# DIGITAL_IO.net
KiCad netlist of a schematic drawn in Altium Designer
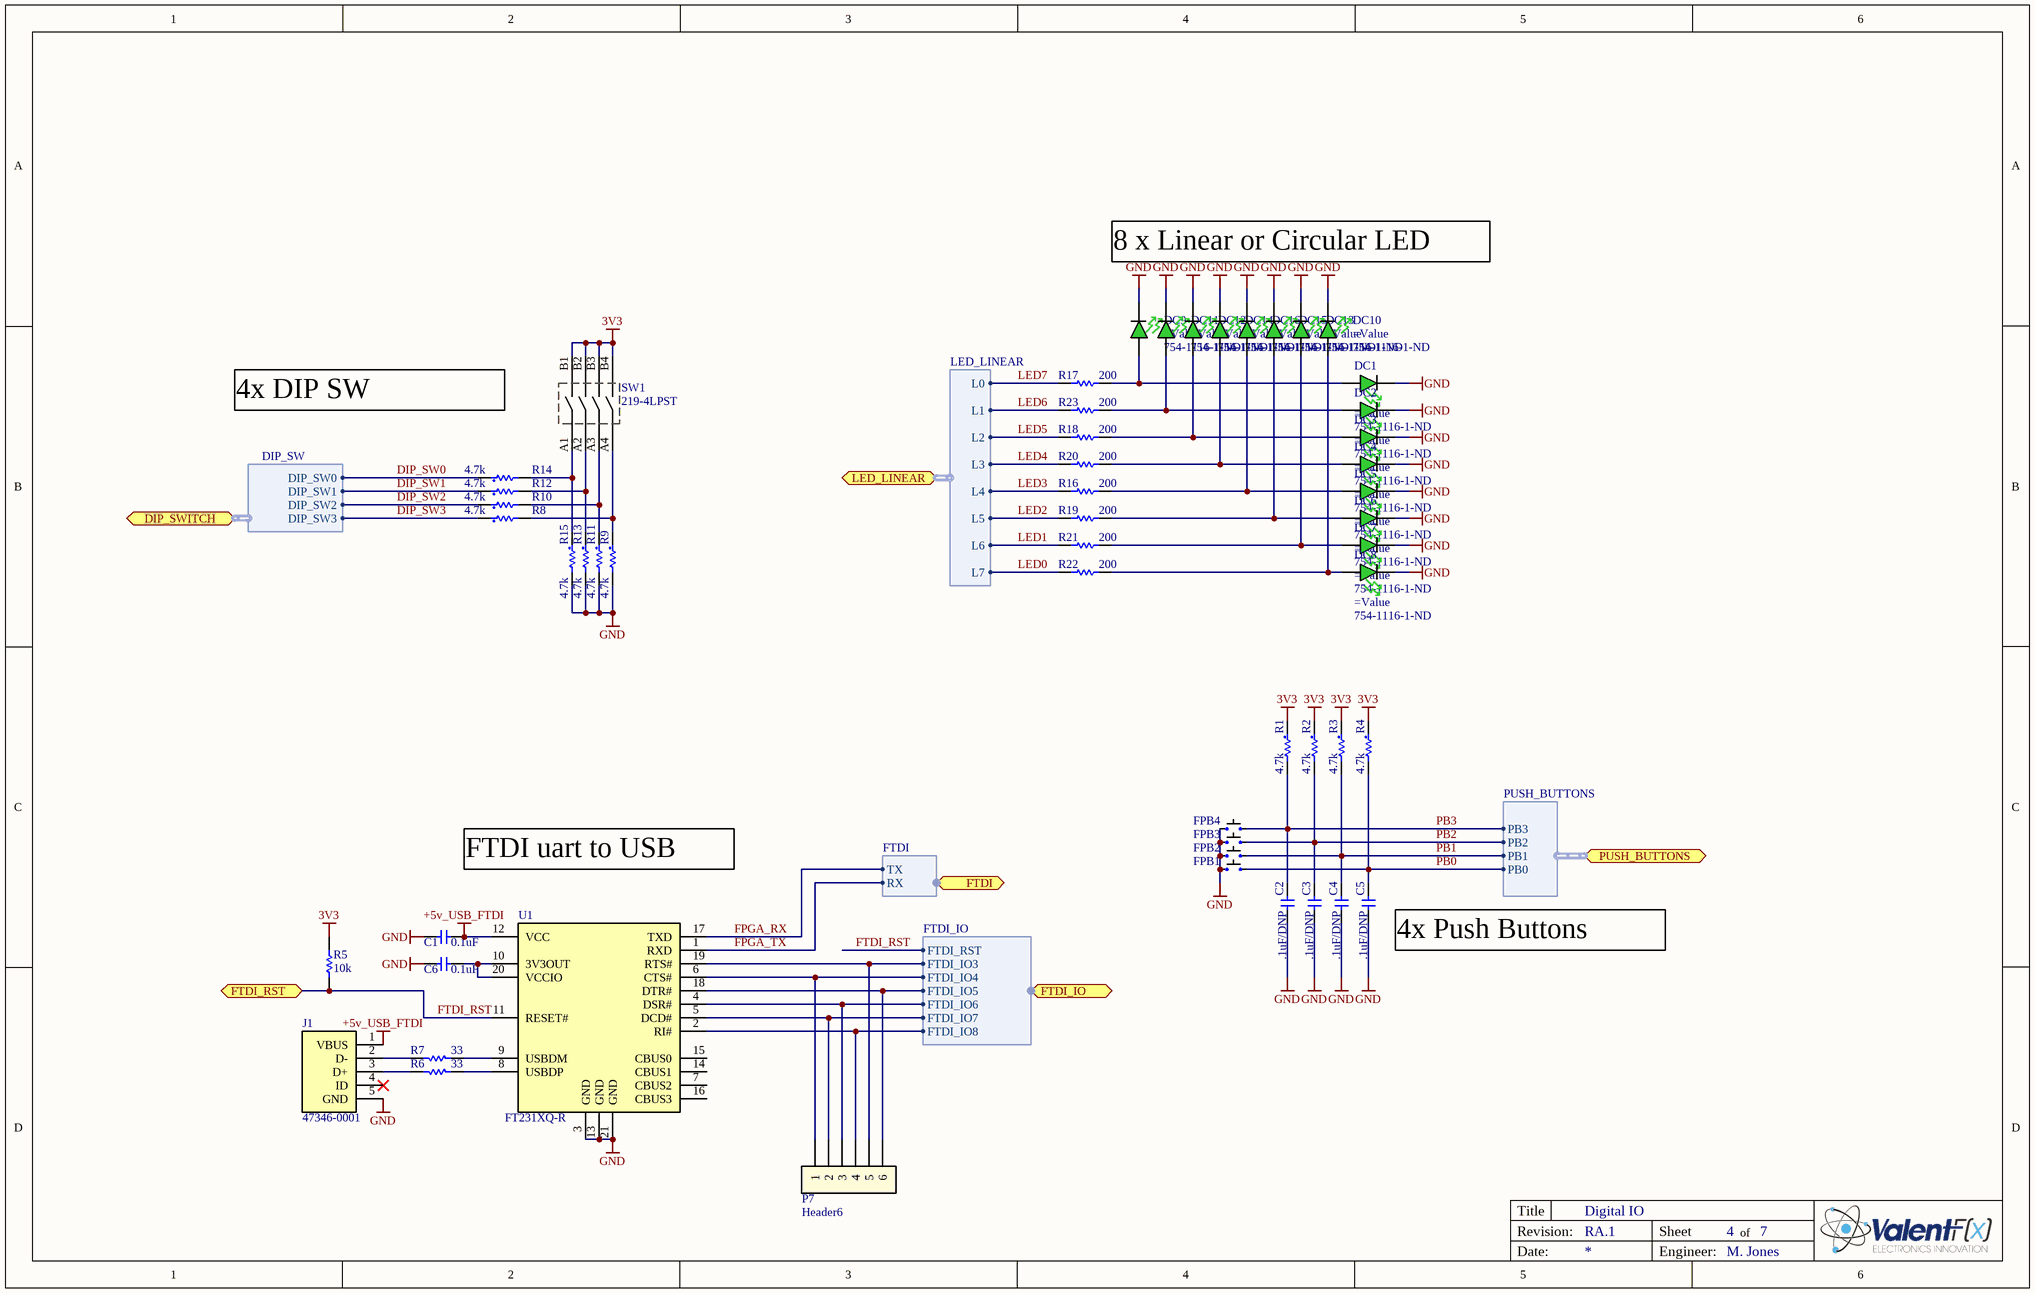
[diagram p0: DIGITAL_IO.SchDoc]

(export (version "E")
  (design (tool "Eeschema 10.0.6"))
  (components
    (comp (ref "C1")
      (value "0.1uF")
      (footprint "C0603")
      (description "CAP CER .1UF 50V 10% X7R 0603")
      (fields
        (field (name "MANUFACTURER") "Murata Electronics North America")
        (field (name "MANUFACTURER PART NUMBER") "GRM188R71H104KA93D")
      )
      (libsource (lib "Capacitors") (part "GRM188R71H104KA93D"))
    )
    (comp (ref "C2")
      (value ".1uF/DNP")
      (footprint "C0603")
      (description "CAP CER .1UF 50V 10% X7R 0603")
      (fields
        (field (name "MANUFACTURER") "Murata Electronics North America")
        (field (name "MANUFACTURER PART NUMBER") "GRM188R71H104KA93D")
      )
      (libsource (lib "Capacitors") (part "GRM188R71H104KA93D"))
    )
    (comp (ref "C3")
      (value ".1uF/DNP")
      (footprint "C0603")
      (description "CAP CER .1UF 50V 10% X7R 0603")
      (fields
        (field (name "MANUFACTURER") "Murata Electronics North America")
        (field (name "MANUFACTURER PART NUMBER") "GRM188R71H104KA93D")
      )
      (libsource (lib "Capacitors") (part "GRM188R71H104KA93D"))
    )
    (comp (ref "C4")
      (value ".1uF/DNP")
      (footprint "C0603")
      (description "CAP CER .1UF 50V 10% X7R 0603")
      (fields
        (field (name "MANUFACTURER") "Murata Electronics North America")
        (field (name "MANUFACTURER PART NUMBER") "GRM188R71H104KA93D")
      )
      (libsource (lib "Capacitors") (part "GRM188R71H104KA93D"))
    )
    (comp (ref "C5")
      (value ".1uF/DNP")
      (footprint "C0603")
      (description "CAP CER .1UF 50V 10% X7R 0603")
      (fields
        (field (name "MANUFACTURER") "Murata Electronics North America")
        (field (name "MANUFACTURER PART NUMBER") "GRM188R71H104KA93D")
      )
      (libsource (lib "Capacitors") (part "GRM188R71H104KA93D"))
    )
    (comp (ref "C6")
      (value "0.1uF")
      (footprint "C0603")
      (description "CAP CER .1UF 50V 10% X7R 0603")
      (fields
        (field (name "MANUFACTURER") "Murata Electronics North America")
        (field (name "MANUFACTURER PART NUMBER") "GRM188R71H104KA93D")
      )
      (libsource (lib "Capacitors") (part "GRM188R71H104KA93D"))
    )
    (comp (ref "DC1")
      (value "~")
      (footprint "LED_0603 - GREEN")
      (description "LED 1.6X0.8MM 570NM GRN CLR SMD")
      (fields
        (field (name "SUPPLIER PART NUMBER 1") "754-1116-1-ND")
        (field (name "MANUFACTURER") "Kingbright Corp")
        (field (name "MANUFACTURER PART NUMBER") "APT1608CGCK")
      )
      (libsource (lib "mDiode") (part "APT1608CGCK"))
    )
    (comp (ref "DC2")
      (value "~")
      (footprint "LED_0603 - GREEN")
      (description "LED 1.6X0.8MM 570NM GRN CLR SMD")
      (fields
        (field (name "SUPPLIER PART NUMBER 1") "754-1116-1-ND")
        (field (name "MANUFACTURER") "Kingbright Corp")
        (field (name "MANUFACTURER PART NUMBER") "APT1608CGCK")
      )
      (libsource (lib "mDiode") (part "APT1608CGCK"))
    )
    (comp (ref "DC3")
      (value "~")
      (footprint "LED_0603 - GREEN")
      (description "LED 1.6X0.8MM 570NM GRN CLR SMD")
      (fields
        (field (name "SUPPLIER PART NUMBER 1") "754-1116-1-ND")
        (field (name "MANUFACTURER") "Kingbright Corp")
        (field (name "MANUFACTURER PART NUMBER") "APT1608CGCK")
      )
      (libsource (lib "mDiode") (part "APT1608CGCK"))
    )
    (comp (ref "DC4")
      (value "~")
      (footprint "LED_0603 - GREEN")
      (description "LED 1.6X0.8MM 570NM GRN CLR SMD")
      (fields
        (field (name "SUPPLIER PART NUMBER 1") "754-1116-1-ND")
        (field (name "MANUFACTURER") "Kingbright Corp")
        (field (name "MANUFACTURER PART NUMBER") "APT1608CGCK")
      )
      (libsource (lib "mDiode") (part "APT1608CGCK"))
    )
    (comp (ref "DC5")
      (value "~")
      (footprint "LED_0603 - GREEN")
      (description "LED 1.6X0.8MM 570NM GRN CLR SMD")
      (fields
        (field (name "SUPPLIER PART NUMBER 1") "754-1116-1-ND")
        (field (name "MANUFACTURER") "Kingbright Corp")
        (field (name "MANUFACTURER PART NUMBER") "APT1608CGCK")
      )
      (libsource (lib "mDiode") (part "APT1608CGCK"))
    )
    (comp (ref "DC6")
      (value "~")
      (footprint "LED_0603 - GREEN")
      (description "LED 1.6X0.8MM 570NM GRN CLR SMD")
      (fields
        (field (name "SUPPLIER PART NUMBER 1") "754-1116-1-ND")
        (field (name "MANUFACTURER") "Kingbright Corp")
        (field (name "MANUFACTURER PART NUMBER") "APT1608CGCK")
      )
      (libsource (lib "mDiode") (part "APT1608CGCK"))
    )
    (comp (ref "DC7")
      (value "~")
      (footprint "LED_0603 - GREEN")
      (description "LED 1.6X0.8MM 570NM GRN CLR SMD")
      (fields
        (field (name "SUPPLIER PART NUMBER 1") "754-1116-1-ND")
        (field (name "MANUFACTURER") "Kingbright Corp")
        (field (name "MANUFACTURER PART NUMBER") "APT1608CGCK")
      )
      (libsource (lib "mDiode") (part "APT1608CGCK"))
    )
    (comp (ref "DC8")
      (value "~")
      (footprint "LED_0603 - GREEN")
      (description "LED 1.6X0.8MM 570NM GRN CLR SMD")
      (fields
        (field (name "SUPPLIER PART NUMBER 1") "754-1116-1-ND")
        (field (name "MANUFACTURER") "Kingbright Corp")
        (field (name "MANUFACTURER PART NUMBER") "APT1608CGCK")
      )
      (libsource (lib "mDiode") (part "APT1608CGCK"))
    )
    (comp (ref "DC9")
      (value "~")
      (footprint "LED_0603 - GREEN")
      (description "LED 1.6X0.8MM 570NM GRN CLR SMD")
      (fields
        (field (name "SUPPLIER PART NUMBER 1") "754-1116-1-ND")
        (field (name "MANUFACTURER") "Kingbright Corp")
        (field (name "MANUFACTURER PART NUMBER") "APT1608CGCK")
      )
      (libsource (lib "mDiode") (part "APT1608CGCK"))
    )
    (comp (ref "DC10")
      (value "~")
      (footprint "LED_0603 - GREEN")
      (description "LED 1.6X0.8MM 570NM GRN CLR SMD")
      (fields
        (field (name "SUPPLIER PART NUMBER 1") "754-1116-1-ND")
        (field (name "MANUFACTURER") "Kingbright Corp")
        (field (name "MANUFACTURER PART NUMBER") "APT1608CGCK")
      )
      (libsource (lib "mDiode") (part "APT1608CGCK"))
    )
    (comp (ref "DC11")
      (value "~")
      (footprint "LED_0603 - GREEN")
      (description "LED 1.6X0.8MM 570NM GRN CLR SMD")
      (fields
        (field (name "SUPPLIER PART NUMBER 1") "754-1116-1-ND")
        (field (name "MANUFACTURER") "Kingbright Corp")
        (field (name "MANUFACTURER PART NUMBER") "APT1608CGCK")
      )
      (libsource (lib "mDiode") (part "APT1608CGCK"))
    )
    (comp (ref "DC12")
      (value "~")
      (footprint "LED_0603 - GREEN")
      (description "LED 1.6X0.8MM 570NM GRN CLR SMD")
      (fields
        (field (name "SUPPLIER PART NUMBER 1") "754-1116-1-ND")
        (field (name "MANUFACTURER") "Kingbright Corp")
        (field (name "MANUFACTURER PART NUMBER") "APT1608CGCK")
      )
      (libsource (lib "mDiode") (part "APT1608CGCK"))
    )
    (comp (ref "DC13")
      (value "~")
      (footprint "LED_0603 - GREEN")
      (description "LED 1.6X0.8MM 570NM GRN CLR SMD")
      (fields
        (field (name "SUPPLIER PART NUMBER 1") "754-1116-1-ND")
        (field (name "MANUFACTURER") "Kingbright Corp")
        (field (name "MANUFACTURER PART NUMBER") "APT1608CGCK")
      )
      (libsource (lib "mDiode") (part "APT1608CGCK"))
    )
    (comp (ref "DC14")
      (value "~")
      (footprint "LED_0603 - GREEN")
      (description "LED 1.6X0.8MM 570NM GRN CLR SMD")
      (fields
        (field (name "SUPPLIER PART NUMBER 1") "754-1116-1-ND")
        (field (name "MANUFACTURER") "Kingbright Corp")
        (field (name "MANUFACTURER PART NUMBER") "APT1608CGCK")
      )
      (libsource (lib "mDiode") (part "APT1608CGCK"))
    )
    (comp (ref "DC15")
      (value "~")
      (footprint "LED_0603 - GREEN")
      (description "LED 1.6X0.8MM 570NM GRN CLR SMD")
      (fields
        (field (name "SUPPLIER PART NUMBER 1") "754-1116-1-ND")
        (field (name "MANUFACTURER") "Kingbright Corp")
        (field (name "MANUFACTURER PART NUMBER") "APT1608CGCK")
      )
      (libsource (lib "mDiode") (part "APT1608CGCK"))
    )
    (comp (ref "DC16")
      (value "~")
      (footprint "LED_0603 - GREEN")
      (description "LED 1.6X0.8MM 570NM GRN CLR SMD")
      (fields
        (field (name "SUPPLIER PART NUMBER 1") "754-1116-1-ND")
        (field (name "MANUFACTURER") "Kingbright Corp")
        (field (name "MANUFACTURER PART NUMBER") "APT1608CGCK")
      )
      (libsource (lib "mDiode") (part "APT1608CGCK"))
    )
    (comp (ref "FPB1")
      (value "~")
      (footprint "mElectroMechanical:FSM4JSMA")
      (description "SWITCH TACTILE SPST-NO 0.05A 12V")
      (fields
        (field (name "MANUFACTURER") "TE Connectivity")
        (field (name "MANUFACTURER PART NUMBER") "FSM4JSMA")
      )
      (libsource (lib "mElectroMechanical") (part "FSM4JSMATR"))
    )
    (comp (ref "FPB2")
      (value "~")
      (footprint "mElectroMechanical:FSM4JSMA")
      (description "SWITCH TACTILE SPST-NO 0.05A 12V")
      (fields
        (field (name "MANUFACTURER") "TE Connectivity")
        (field (name "MANUFACTURER PART NUMBER") "FSM4JSMA")
      )
      (libsource (lib "mElectroMechanical") (part "FSM4JSMATR"))
    )
    (comp (ref "FPB3")
      (value "~")
      (footprint "mElectroMechanical:FSM4JSMA")
      (description "SWITCH TACTILE SPST-NO 0.05A 12V")
      (fields
        (field (name "MANUFACTURER") "TE Connectivity")
        (field (name "MANUFACTURER PART NUMBER") "FSM4JSMA")
      )
      (libsource (lib "mElectroMechanical") (part "FSM4JSMATR"))
    )
    (comp (ref "FPB4")
      (value "~")
      (footprint "mElectroMechanical:FSM4JSMA")
      (description "SWITCH TACTILE SPST-NO 0.05A 12V")
      (fields
        (field (name "MANUFACTURER") "TE Connectivity")
        (field (name "MANUFACTURER PART NUMBER") "FSM4JSMA")
      )
      (libsource (lib "mElectroMechanical") (part "FSM4JSMATR"))
    )
    (comp (ref "J1")
      (value "47346-0001")
      (footprint "USB - 47346-0001")
      (description "Micro B CONN RCPT 5POS MICRO B USB R/A")
      (fields
        (field (name "MANUFACTURER") "Molex Inc")
        (field (name "MANUFACTURER PART NUMBER") "0473460001")
      )
      (libsource (lib "mConnector") (part "USB - 0473460001"))
    )
    (comp (ref "P7")
      (value "Header6")
      (footprint "HEADER_6_30_100 SMT SIP")
      (description "Header 6 pin")
      (libsource (lib "mConnector") (part "Header6"))
    )
    (comp (ref "R1")
      (value "4.7k")
      (footprint "mRCL:R0603")
      (description "4.7k Thick Film Resistors - SMD 1/10watt 4.7Kohms 1%")
      (fields
        (field (name "MANUFACTURER") "Vishay Dale")
        (field (name "MANUFACTURER PART NUMBER") "CRCW06034K70FKEA")
      )
      (libsource (lib "mResistors") (part "R0603 - CRCW06034K70FKEA"))
    )
    (comp (ref "R2")
      (value "4.7k")
      (footprint "mRCL:R0603")
      (description "4.7k Thick Film Resistors - SMD 1/10watt 4.7Kohms 1%")
      (fields
        (field (name "MANUFACTURER") "Vishay Dale")
        (field (name "MANUFACTURER PART NUMBER") "CRCW06034K70FKEA")
      )
      (libsource (lib "mResistors") (part "R0603 - CRCW06034K70FKEA"))
    )
    (comp (ref "R3")
      (value "4.7k")
      (footprint "mRCL:R0603")
      (description "4.7k Thick Film Resistors - SMD 1/10watt 4.7Kohms 1%")
      (fields
        (field (name "MANUFACTURER") "Vishay Dale")
        (field (name "MANUFACTURER PART NUMBER") "CRCW06034K70FKEA")
      )
      (libsource (lib "mResistors") (part "R0603 - CRCW06034K70FKEA"))
    )
    (comp (ref "R4")
      (value "4.7k")
      (footprint "mRCL:R0603")
      (description "4.7k Thick Film Resistors - SMD 1/10watt 4.7Kohms 1%")
      (fields
        (field (name "MANUFACTURER") "Vishay Dale")
        (field (name "MANUFACTURER PART NUMBER") "CRCW06034K70FKEA")
      )
      (libsource (lib "mResistors") (part "R0603 - CRCW06034K70FKEA"))
    )
    (comp (ref "R5")
      (value "10k")
      (footprint "R0603")
      (description "RES 10.0K OHM 1/10W 1% 0603 SMD")
      (fields
        (field (name "MANUFACTURER") "Panasonic - ECG")
        (field (name "TOLERANCE") "±1%")
        (field (name "SOURCE") "Digikey")
      )
      (libsource (lib "Resistors") (part "ERJ-3EKF1002V"))
    )
    (comp (ref "R6")
      (value "33")
      (footprint "R0603")
      (description "RES 33.0 OHM 1/10W 1% 0603 SMD")
      (fields
        (field (name "MANUFACTURER") "Panasonic - ECG")
        (field (name "MANUFACTURER PART NUMBER") "ERJ-3EKF33R0V")
      )
      (libsource (lib "eResistors") (part "ERJ-3EKF33R0V"))
    )
    (comp (ref "R7")
      (value "33")
      (footprint "R0603")
      (description "RES 33.0 OHM 1/10W 1% 0603 SMD")
      (fields
        (field (name "MANUFACTURER") "Panasonic - ECG")
        (field (name "MANUFACTURER PART NUMBER") "ERJ-3EKF33R0V")
      )
      (libsource (lib "eResistors") (part "ERJ-3EKF33R0V"))
    )
    (comp (ref "R8")
      (value "4.7k")
      (footprint "mRCL:R0603")
      (description "4.7k Thick Film Resistors - SMD 1/10watt 4.7Kohms 1%")
      (fields
        (field (name "MANUFACTURER") "Vishay Dale")
        (field (name "MANUFACTURER PART NUMBER") "CRCW06034K70FKEA")
      )
      (libsource (lib "mResistors") (part "R0603 - CRCW06034K70FKEA"))
    )
    (comp (ref "R9")
      (value "4.7k")
      (footprint "mRCL:R0603")
      (description "4.7k Thick Film Resistors - SMD 1/10watt 4.7Kohms 1%")
      (fields
        (field (name "MANUFACTURER") "Vishay Dale")
        (field (name "MANUFACTURER PART NUMBER") "CRCW06034K70FKEA")
      )
      (libsource (lib "mResistors") (part "R0603 - CRCW06034K70FKEA"))
    )
    (comp (ref "R10")
      (value "4.7k")
      (footprint "mRCL:R0603")
      (description "4.7k Thick Film Resistors - SMD 1/10watt 4.7Kohms 1%")
      (fields
        (field (name "MANUFACTURER") "Vishay Dale")
        (field (name "MANUFACTURER PART NUMBER") "CRCW06034K70FKEA")
      )
      (libsource (lib "mResistors") (part "R0603 - CRCW06034K70FKEA"))
    )
    (comp (ref "R11")
      (value "4.7k")
      (footprint "mRCL:R0603")
      (description "4.7k Thick Film Resistors - SMD 1/10watt 4.7Kohms 1%")
      (fields
        (field (name "MANUFACTURER") "Vishay Dale")
        (field (name "MANUFACTURER PART NUMBER") "CRCW06034K70FKEA")
      )
      (libsource (lib "mResistors") (part "R0603 - CRCW06034K70FKEA"))
    )
    (comp (ref "R12")
      (value "4.7k")
      (footprint "mRCL:R0603")
      (description "4.7k Thick Film Resistors - SMD 1/10watt 4.7Kohms 1%")
      (fields
        (field (name "MANUFACTURER") "Vishay Dale")
        (field (name "MANUFACTURER PART NUMBER") "CRCW06034K70FKEA")
      )
      (libsource (lib "mResistors") (part "R0603 - CRCW06034K70FKEA"))
    )
    (comp (ref "R13")
      (value "4.7k")
      (footprint "mRCL:R0603")
      (description "4.7k Thick Film Resistors - SMD 1/10watt 4.7Kohms 1%")
      (fields
        (field (name "MANUFACTURER") "Vishay Dale")
        (field (name "MANUFACTURER PART NUMBER") "CRCW06034K70FKEA")
      )
      (libsource (lib "mResistors") (part "R0603 - CRCW06034K70FKEA"))
    )
    (comp (ref "R14")
      (value "4.7k")
      (footprint "mRCL:R0603")
      (description "4.7k Thick Film Resistors - SMD 1/10watt 4.7Kohms 1%")
      (fields
        (field (name "MANUFACTURER") "Vishay Dale")
        (field (name "MANUFACTURER PART NUMBER") "CRCW06034K70FKEA")
      )
      (libsource (lib "mResistors") (part "R0603 - CRCW06034K70FKEA"))
    )
    (comp (ref "R15")
      (value "4.7k")
      (footprint "mRCL:R0603")
      (description "4.7k Thick Film Resistors - SMD 1/10watt 4.7Kohms 1%")
      (fields
        (field (name "MANUFACTURER") "Vishay Dale")
        (field (name "MANUFACTURER PART NUMBER") "CRCW06034K70FKEA")
      )
      (libsource (lib "mResistors") (part "R0603 - CRCW06034K70FKEA"))
    )
    (comp (ref "R16")
      (value "200")
      (footprint "R0603")
      (description "RES 200 OHM 1/10W 1% 0603 SMD")
      (fields
        (field (name "MANUFACTURER") "Panasonic - ECG")
        (field (name "MANUFACTURER PART NUMBER") "ERJ-3EKF2000V")
      )
      (libsource (lib "eResistors") (part "ERJ-3EKF2000V"))
    )
    (comp (ref "R17")
      (value "200")
      (footprint "R0603")
      (description "RES 200 OHM 1/10W 1% 0603 SMD")
      (fields
        (field (name "MANUFACTURER") "Panasonic - ECG")
        (field (name "MANUFACTURER PART NUMBER") "ERJ-3EKF2000V")
      )
      (libsource (lib "eResistors") (part "ERJ-3EKF2000V"))
    )
    (comp (ref "R18")
      (value "200")
      (footprint "R0603")
      (description "RES 200 OHM 1/10W 1% 0603 SMD")
      (fields
        (field (name "MANUFACTURER") "Panasonic - ECG")
        (field (name "MANUFACTURER PART NUMBER") "ERJ-3EKF2000V")
      )
      (libsource (lib "eResistors") (part "ERJ-3EKF2000V"))
    )
    (comp (ref "R19")
      (value "200")
      (footprint "R0603")
      (description "RES 200 OHM 1/10W 1% 0603 SMD")
      (fields
        (field (name "MANUFACTURER") "Panasonic - ECG")
        (field (name "MANUFACTURER PART NUMBER") "ERJ-3EKF2000V")
      )
      (libsource (lib "eResistors") (part "ERJ-3EKF2000V"))
    )
    (comp (ref "R20")
      (value "200")
      (footprint "R0603")
      (description "RES 200 OHM 1/10W 1% 0603 SMD")
      (fields
        (field (name "MANUFACTURER") "Panasonic - ECG")
        (field (name "MANUFACTURER PART NUMBER") "ERJ-3EKF2000V")
      )
      (libsource (lib "eResistors") (part "ERJ-3EKF2000V"))
    )
    (comp (ref "R21")
      (value "200")
      (footprint "R0603")
      (description "RES 200 OHM 1/10W 1% 0603 SMD")
      (fields
        (field (name "MANUFACTURER") "Panasonic - ECG")
        (field (name "MANUFACTURER PART NUMBER") "ERJ-3EKF2000V")
      )
      (libsource (lib "eResistors") (part "ERJ-3EKF2000V"))
    )
    (comp (ref "R22")
      (value "200")
      (footprint "R0603")
      (description "RES 200 OHM 1/10W 1% 0603 SMD")
      (fields
        (field (name "MANUFACTURER") "Panasonic - ECG")
        (field (name "MANUFACTURER PART NUMBER") "ERJ-3EKF2000V")
      )
      (libsource (lib "eResistors") (part "ERJ-3EKF2000V"))
    )
    (comp (ref "R23")
      (value "200")
      (footprint "R0603")
      (description "RES 200 OHM 1/10W 1% 0603 SMD")
      (fields
        (field (name "MANUFACTURER") "Panasonic - ECG")
        (field (name "MANUFACTURER PART NUMBER") "ERJ-3EKF2000V")
      )
      (libsource (lib "eResistors") (part "ERJ-3EKF2000V"))
    )
    (comp (ref "SW1")
      (value "219-4LPST")
      (footprint "ADE04S04")
      (description "SWITCH TAPE SEAL 4 POS SMD")
      (fields (field (name "MANUFACTURER") "CTS Electrocomponents"))
      (libsource (lib "mElectroMechanical") (part "DIP SW - 219-4LPST"))
    )
    (comp (ref "U1")
      (value "FT231XQ-R")
      (footprint "QFN-20_L")
      (description "IC USB SERIAL FULL UART QFN-20")
      (fields (field (name "MANUFACTURER") "FTDI, Future Technology Devices International Ltd"))
      (libsource (lib "mIC") (part "USB - FT231XQ-R"))
    )
  )
  (nets
    (net (code "6") (name "+5v_USB_FTDI") (class "Default")
      (node (ref "C1") (pin "2") (pinfunction "2_2") (pintype "passive"))
      (node (ref "J1") (pin "1") (pinfunction "VBUS_1") (pintype "passive"))
      (node (ref "U1") (pin "12") (pinfunction "VCC_12") (pintype "passive"))
    )
    (net (code "7") (name "/DIP_SW0") (class "Default")
      (node (ref "R14") (pin "1") (pinfunction "1_1") (pintype "passive"))
    )
    (net (code "8") (name "/DIP_SW1") (class "Default")
      (node (ref "R12") (pin "1") (pinfunction "1_1") (pintype "passive"))
    )
    (net (code "9") (name "/DIP_SW2") (class "Default")
      (node (ref "R10") (pin "1") (pinfunction "1_1") (pintype "passive"))
    )
    (net (code "10") (name "/DIP_SW3") (class "Default")
      (node (ref "R8") (pin "1") (pinfunction "1_1") (pintype "passive"))
    )
    (net (code "11") (name "/FPGA_RX") (class "Default")
      (node (ref "U1") (pin "17") (pinfunction "TXD_17") (pintype "passive"))
    )
    (net (code "12") (name "/FPGA_TX") (class "Default")
      (node (ref "U1") (pin "1") (pinfunction "RXD_1") (pintype "passive"))
    )
    (net (code "13") (name "/FTDI_RST") (class "Default")
      (node (ref "R5") (pin "2") (pinfunction "2_2") (pintype "passive"))
      (node (ref "U1") (pin "11") (pinfunction "RESET#_11") (pintype "passive"))
    )
    (net (code "14") (name "/LED0") (class "Default")
      (node (ref "R22") (pin "2") (pinfunction "2_2") (pintype "passive"))
    )
    (net (code "15") (name "/LED1") (class "Default")
      (node (ref "R21") (pin "2") (pinfunction "2_2") (pintype "passive"))
    )
    (net (code "16") (name "/LED2") (class "Default")
      (node (ref "R19") (pin "2") (pinfunction "2_2") (pintype "passive"))
    )
    (net (code "17") (name "/LED3") (class "Default")
      (node (ref "R16") (pin "2") (pinfunction "2_2") (pintype "passive"))
    )
    (net (code "18") (name "/LED4") (class "Default")
      (node (ref "R20") (pin "2") (pinfunction "2_2") (pintype "passive"))
    )
    (net (code "19") (name "/LED5") (class "Default")
      (node (ref "R18") (pin "2") (pinfunction "2_2") (pintype "passive"))
    )
    (net (code "20") (name "/LED6") (class "Default")
      (node (ref "R23") (pin "2") (pinfunction "2_2") (pintype "passive"))
    )
    (net (code "21") (name "/LED7") (class "Default")
      (node (ref "R17") (pin "2") (pinfunction "2_2") (pintype "passive"))
    )
    (net (code "22") (name "/PB0") (class "Default")
      (node (ref "C5") (pin "1") (pinfunction "1_1") (pintype "passive"))
      (node (ref "FPB1") (pin "B") (pinfunction "B_B") (pintype "passive"))
      (node (ref "R4") (pin "2") (pinfunction "2_2") (pintype "passive"))
    )
    (net (code "23") (name "/PB1") (class "Default")
      (node (ref "C4") (pin "1") (pinfunction "1_1") (pintype "passive"))
      (node (ref "FPB2") (pin "B") (pinfunction "B_B") (pintype "passive"))
      (node (ref "R3") (pin "2") (pinfunction "2_2") (pintype "passive"))
    )
    (net (code "24") (name "/PB2") (class "Default")
      (node (ref "C3") (pin "1") (pinfunction "1_1") (pintype "passive"))
      (node (ref "FPB3") (pin "B") (pinfunction "B_B") (pintype "passive"))
      (node (ref "R2") (pin "2") (pinfunction "2_2") (pintype "passive"))
    )
    (net (code "25") (name "/PB3") (class "Default")
      (node (ref "C2") (pin "1") (pinfunction "1_1") (pintype "passive"))
      (node (ref "FPB4") (pin "B") (pinfunction "B_B") (pintype "passive"))
      (node (ref "R1") (pin "2") (pinfunction "2_2") (pintype "passive"))
    )
    (net (code "31") (name "3V3") (class "Default")
      (node (ref "R1") (pin "1") (pinfunction "1_1") (pintype "passive"))
      (node (ref "R2") (pin "1") (pinfunction "1_1") (pintype "passive"))
      (node (ref "R3") (pin "1") (pinfunction "1_1") (pintype "passive"))
      (node (ref "R4") (pin "1") (pinfunction "1_1") (pintype "passive"))
      (node (ref "R5") (pin "1") (pinfunction "1_1") (pintype "passive"))
      (node (ref "SW1") (pin "B1") (pinfunction "B1_B1") (pintype "passive"))
      (node (ref "SW1") (pin "B2") (pinfunction "B2_B2") (pintype "passive"))
      (node (ref "SW1") (pin "B3") (pinfunction "B3_B3") (pintype "passive"))
      (node (ref "SW1") (pin "B4") (pinfunction "B4_B4") (pintype "passive"))
    )
    (net (code "32") (name "GND") (class "Default")
      (node (ref "C1") (pin "1") (pinfunction "1_1") (pintype "passive"))
      (node (ref "C2") (pin "2") (pinfunction "2_2") (pintype "passive"))
      (node (ref "C3") (pin "2") (pinfunction "2_2") (pintype "passive"))
      (node (ref "C4") (pin "2") (pinfunction "2_2") (pintype "passive"))
      (node (ref "C5") (pin "2") (pinfunction "2_2") (pintype "passive"))
      (node (ref "C6") (pin "1") (pinfunction "1_1") (pintype "passive"))
      (node (ref "DC1") (pin "C") (pinfunction "C_C") (pintype "passive"))
      (node (ref "DC10") (pin "C") (pinfunction "C_C") (pintype "passive"))
      (node (ref "DC11") (pin "C") (pinfunction "C_C") (pintype "passive"))
      (node (ref "DC12") (pin "C") (pinfunction "C_C") (pintype "passive"))
      (node (ref "DC13") (pin "C") (pinfunction "C_C") (pintype "passive"))
      (node (ref "DC14") (pin "C") (pinfunction "C_C") (pintype "passive"))
      (node (ref "DC15") (pin "C") (pinfunction "C_C") (pintype "passive"))
      (node (ref "DC16") (pin "C") (pinfunction "C_C") (pintype "passive"))
      (node (ref "DC2") (pin "C") (pinfunction "C_C") (pintype "passive"))
      (node (ref "DC3") (pin "C") (pinfunction "C_C") (pintype "passive"))
      (node (ref "DC4") (pin "C") (pinfunction "C_C") (pintype "passive"))
      (node (ref "DC5") (pin "C") (pinfunction "C_C") (pintype "passive"))
      (node (ref "DC6") (pin "C") (pinfunction "C_C") (pintype "passive"))
      (node (ref "DC7") (pin "C") (pinfunction "C_C") (pintype "passive"))
      (node (ref "DC8") (pin "C") (pinfunction "C_C") (pintype "passive"))
      (node (ref "DC9") (pin "C") (pinfunction "C_C") (pintype "passive"))
      (node (ref "FPB1") (pin "A") (pinfunction "A_A") (pintype "passive"))
      (node (ref "FPB2") (pin "A") (pinfunction "A_A") (pintype "passive"))
      (node (ref "FPB3") (pin "A") (pinfunction "A_A") (pintype "passive"))
      (node (ref "FPB4") (pin "A") (pinfunction "A_A") (pintype "passive"))
      (node (ref "J1") (pin "5") (pinfunction "GND_5") (pintype "passive"))
      (node (ref "R11") (pin "2") (pinfunction "2_2") (pintype "passive"))
      (node (ref "R13") (pin "2") (pinfunction "2_2") (pintype "passive"))
      (node (ref "R15") (pin "2") (pinfunction "2_2") (pintype "passive"))
      (node (ref "R9") (pin "2") (pinfunction "2_2") (pintype "passive"))
      (node (ref "U1") (pin "13") (pinfunction "GND_13") (pintype "passive"))
      (node (ref "U1") (pin "21") (pinfunction "GND_21") (pintype "passive"))
      (node (ref "U1") (pin "3") (pinfunction "GND_3") (pintype "passive"))
    )
    (net (code "33") (name "Net-(DC1-PadA)") (class "Default")
      (node (ref "DC1") (pin "A") (pinfunction "A_A") (pintype "passive"))
      (node (ref "DC9") (pin "A") (pinfunction "A_A") (pintype "passive"))
      (node (ref "R17") (pin "1") (pinfunction "1_1") (pintype "passive"))
    )
    (net (code "34") (name "Net-(DC10-PadA)") (class "Default")
      (node (ref "DC10") (pin "A") (pinfunction "A_A") (pintype "passive"))
      (node (ref "DC8") (pin "A") (pinfunction "A_A") (pintype "passive"))
      (node (ref "R22") (pin "1") (pinfunction "1_1") (pintype "passive"))
    )
    (net (code "35") (name "Net-(DC11-PadA)") (class "Default")
      (node (ref "DC11") (pin "A") (pinfunction "A_A") (pintype "passive"))
      (node (ref "DC2") (pin "A") (pinfunction "A_A") (pintype "passive"))
      (node (ref "R23") (pin "1") (pinfunction "1_1") (pintype "passive"))
    )
    (net (code "36") (name "Net-(DC12-PadA)") (class "Default")
      (node (ref "DC12") (pin "A") (pinfunction "A_A") (pintype "passive"))
      (node (ref "DC3") (pin "A") (pinfunction "A_A") (pintype "passive"))
      (node (ref "R18") (pin "1") (pinfunction "1_1") (pintype "passive"))
    )
    (net (code "37") (name "Net-(DC13-PadA)") (class "Default")
      (node (ref "DC13") (pin "A") (pinfunction "A_A") (pintype "passive"))
      (node (ref "DC7") (pin "A") (pinfunction "A_A") (pintype "passive"))
      (node (ref "R21") (pin "1") (pinfunction "1_1") (pintype "passive"))
    )
    (net (code "38") (name "Net-(DC14-PadA)") (class "Default")
      (node (ref "DC14") (pin "A") (pinfunction "A_A") (pintype "passive"))
      (node (ref "DC4") (pin "A") (pinfunction "A_A") (pintype "passive"))
      (node (ref "R20") (pin "1") (pinfunction "1_1") (pintype "passive"))
    )
    (net (code "39") (name "Net-(DC15-PadA)") (class "Default")
      (node (ref "DC15") (pin "A") (pinfunction "A_A") (pintype "passive"))
      (node (ref "DC6") (pin "A") (pinfunction "A_A") (pintype "passive"))
      (node (ref "R19") (pin "1") (pinfunction "1_1") (pintype "passive"))
    )
    (net (code "40") (name "Net-(DC16-PadA)") (class "Default")
      (node (ref "DC16") (pin "A") (pinfunction "A_A") (pintype "passive"))
      (node (ref "DC5") (pin "A") (pinfunction "A_A") (pintype "passive"))
      (node (ref "R16") (pin "1") (pinfunction "1_1") (pintype "passive"))
    )
    (net (code "41") (name "Net-(J1-D+)") (class "Default")
      (node (ref "J1") (pin "3") (pinfunction "D+_3") (pintype "passive"))
      (node (ref "R6") (pin "2") (pinfunction "2_2") (pintype "passive"))
    )
    (net (code "42") (name "Net-(J1-D-)") (class "Default")
      (node (ref "J1") (pin "2") (pinfunction "D-_2") (pintype "passive"))
      (node (ref "R7") (pin "2") (pinfunction "2_2") (pintype "passive"))
    )
    (net (code "43") (name "Net-(R8-Pad2)") (class "Default")
      (node (ref "R8") (pin "2") (pinfunction "2_2") (pintype "passive"))
      (node (ref "R9") (pin "1") (pinfunction "1_1") (pintype "passive"))
      (node (ref "SW1") (pin "A4") (pinfunction "A4_A4") (pintype "passive"))
    )
    (net (code "44") (name "Net-(R10-Pad2)") (class "Default")
      (node (ref "R10") (pin "2") (pinfunction "2_2") (pintype "passive"))
      (node (ref "R11") (pin "1") (pinfunction "1_1") (pintype "passive"))
      (node (ref "SW1") (pin "A3") (pinfunction "A3_A3") (pintype "passive"))
    )
    (net (code "45") (name "Net-(R12-Pad2)") (class "Default")
      (node (ref "R12") (pin "2") (pinfunction "2_2") (pintype "passive"))
      (node (ref "R13") (pin "1") (pinfunction "1_1") (pintype "passive"))
      (node (ref "SW1") (pin "A2") (pinfunction "A2_A2") (pintype "passive"))
    )
    (net (code "46") (name "Net-(R14-Pad2)") (class "Default")
      (node (ref "R14") (pin "2") (pinfunction "2_2") (pintype "passive"))
      (node (ref "R15") (pin "1") (pinfunction "1_1") (pintype "passive"))
      (node (ref "SW1") (pin "A1") (pinfunction "A1_A1") (pintype "passive"))
    )
    (net (code "47") (name "Net-(U1-3V3OUT)") (class "Default")
      (node (ref "C6") (pin "2") (pinfunction "2_2") (pintype "passive"))
      (node (ref "U1") (pin "10") (pinfunction "3V3OUT_10") (pintype "passive"))
      (node (ref "U1") (pin "20") (pinfunction "VCCIO_20") (pintype "passive"))
    )
    (net (code "48") (name "Net-(U1-CTS#)") (class "Default")
      (node (ref "P7") (pin "1") (pinfunction "1_1") (pintype "passive"))
      (node (ref "U1") (pin "6") (pinfunction "CTS#_6") (pintype "passive"))
    )
    (net (code "49") (name "Net-(U1-DCD#)") (class "Default")
      (node (ref "P7") (pin "2") (pinfunction "2_2") (pintype "passive"))
      (node (ref "U1") (pin "5") (pinfunction "DCD#_5") (pintype "passive"))
    )
    (net (code "50") (name "Net-(U1-DSR#)") (class "Default")
      (node (ref "P7") (pin "3") (pinfunction "3_3") (pintype "passive"))
      (node (ref "U1") (pin "4") (pinfunction "DSR#_4") (pintype "passive"))
    )
    (net (code "51") (name "Net-(U1-DTR#)") (class "Default")
      (node (ref "P7") (pin "6") (pinfunction "6_6") (pintype "passive"))
      (node (ref "U1") (pin "18") (pinfunction "DTR#_18") (pintype "passive"))
    )
    (net (code "52") (name "Net-(U1-RI#)") (class "Default")
      (node (ref "P7") (pin "4") (pinfunction "4_4") (pintype "passive"))
      (node (ref "U1") (pin "2") (pinfunction "RI#_2") (pintype "passive"))
    )
    (net (code "53") (name "Net-(U1-RTS#)") (class "Default")
      (node (ref "P7") (pin "5") (pinfunction "5_5") (pintype "passive"))
      (node (ref "U1") (pin "19") (pinfunction "RTS#_19") (pintype "passive"))
    )
    (net (code "54") (name "Net-(U1-USBDM)") (class "Default")
      (node (ref "R7") (pin "1") (pinfunction "1_1") (pintype "passive"))
      (node (ref "U1") (pin "9") (pinfunction "USBDM_9") (pintype "passive"))
    )
    (net (code "55") (name "Net-(U1-USBDP)") (class "Default")
      (node (ref "R6") (pin "1") (pinfunction "1_1") (pintype "passive"))
      (node (ref "U1") (pin "8") (pinfunction "USBDP_8") (pintype "passive"))
    )
    (net (code "56") (name "unconnected-(J1-ID-Pad4)") (class "Default")
      (node (ref "J1") (pin "4") (pinfunction "ID_4") (pintype "passive+no_connect"))
    )
    (net (code "57") (name "unconnected-(U1-CBUS0-Pad15)") (class "Default")
      (node (ref "U1") (pin "15") (pinfunction "CBUS0_15") (pintype "passive"))
    )
    (net (code "58") (name "unconnected-(U1-CBUS1-Pad14)") (class "Default")
      (node (ref "U1") (pin "14") (pinfunction "CBUS1_14") (pintype "passive"))
    )
    (net (code "59") (name "unconnected-(U1-CBUS2-Pad7)") (class "Default")
      (node (ref "U1") (pin "7") (pinfunction "CBUS2_7") (pintype "passive"))
    )
    (net (code "60") (name "unconnected-(U1-CBUS3-Pad16)") (class "Default")
      (node (ref "U1") (pin "16") (pinfunction "CBUS3_16") (pintype "passive"))
    )
  )
)
